# Multi_HUTSCHIENE_EXT_1_2.net
KiCad netlist of a schematic drawn in Altium Designer
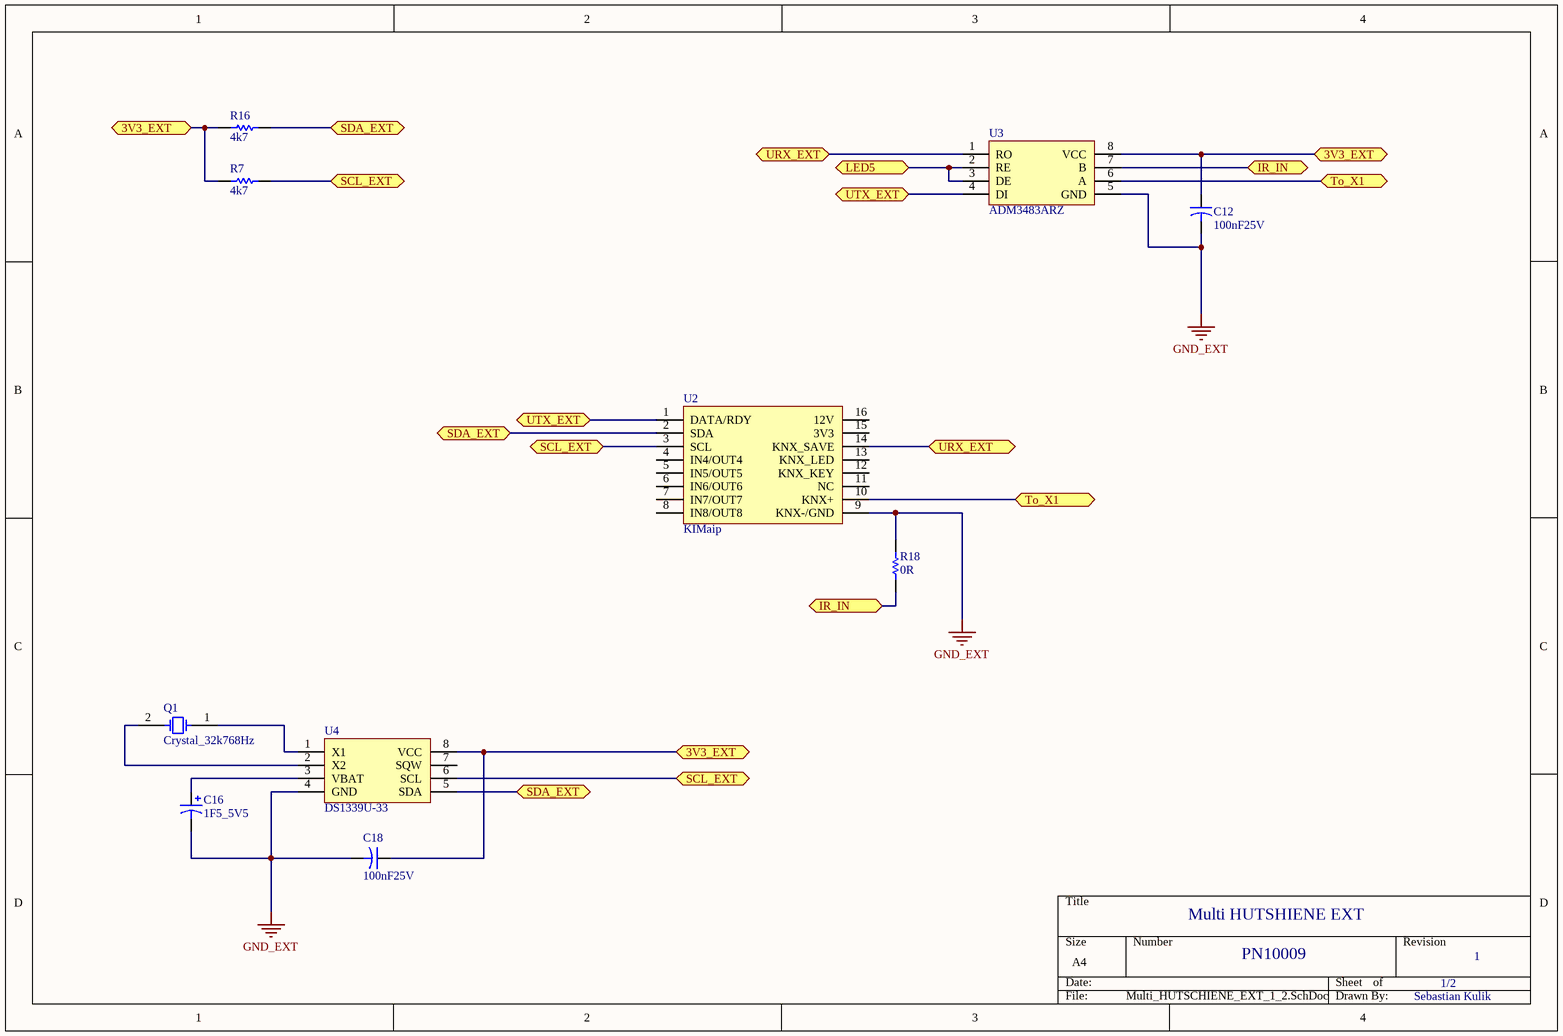
[diagram p0: Multi_HUTSCHIENE_EXT_1_2.SchDoc]

(export (version "E")
  (design (tool "Eeschema 10.0.6"))
  (components
    (comp (ref "C12")
      (value "100nF25V")
      (footprint "C0402")
      (description "AVX, X5R, 10%, 25V")
      (fields
        (field (name "MANUFACTURER") "AVX")
        (field (name "Comment") "100nF25V_0402")
        (field (name "PUBLISHER") "Sebastian Kulik")
      )
      (libsource (lib "Capacitors") (part "100nF25V_0402"))
    )
    (comp (ref "C16")
      (value "1F5_5V5")
      (footprint "Goldcap_B")
      (description "Panasonic, F series")
      (fields
        (field (name "MANUFACTURER") "Panasonic")
        (field (name "Comment") "1F5_5V5_POL")
        (field (name "PUBLISHER") "Sebastian Kulik")
      )
      (libsource (lib "Capacitors") (part "1F5_5V5_POL"))
    )
    (comp (ref "C18")
      (value "100nF25V")
      (footprint "C0402")
      (description "AVX, X5R, 10%, 25V")
      (fields
        (field (name "MANUFACTURER") "AVX")
        (field (name "Comment") "100nF25V_0402")
        (field (name "PUBLISHER") "Sebastian Kulik")
      )
      (libsource (lib "Capacitors") (part "100nF25V_0402"))
    )
    (comp (ref "Q1")
      (value "Crystal_32k768Hz")
      (footprint "VT-200")
      (description "Crystal, 32.768kHz")
      (fields (field (name "MANUFACTURER") "Seiko") (field (name "PUBLISHER") "Sebastian Kulik"))
      (libsource (lib "Passives") (part "Crystal_32k768Hz"))
    )
    (comp (ref "R7")
      (value "4k7")
      (footprint "R0402")
      (description "Vishay CRCW series, 63mW, 1%")
      (fields
        (field (name "MANUFACTURER") "Vishay")
        (field (name "Comment") "4k7_0402")
        (field (name "PUBLISHER") "Sebastian Kulik")
      )
      (libsource (lib "Resistors") (part "4k7_0402"))
    )
    (comp (ref "R16")
      (value "4k7")
      (footprint "R0402")
      (description "Vishay CRCW series, 63mW, 1%")
      (fields
        (field (name "MANUFACTURER") "Vishay")
        (field (name "Comment") "4k7_0402")
        (field (name "PUBLISHER") "Sebastian Kulik")
      )
      (libsource (lib "Resistors") (part "4k7_0402"))
    )
    (comp (ref "R18")
      (value "0R")
      (footprint "R0603(1608)")
      (description "Vishay, CRCW series, 100mW")
      (fields
        (field (name "MANUFACTURER") "Vishay")
        (field (name "Comment") "0R_0603")
        (field (name "PUBLISHER") "Sebastian Kulik")
      )
      (libsource (lib "Resistors") (part "0R_0603"))
    )
    (comp (ref "U2")
      (value "KIMaip")
      (footprint "KIMaip")
      (description "PoE, 12V")
      (fields (field (name "MANUFACTURER") "Tapko") (field (name "PUBLISHER") "Sebastian Kulik"))
      (libsource (lib "ICs") (part "KIMaip"))
    )
    (comp (ref "U3")
      (value "ADM3483ARZ")
      (footprint "SOIC8_N")
      (description "Transceiver, RS485/422")
      (fields (field (name "MANUFACTURER") "ADI") (field (name "PUBLISHER") "Sebastian Kulik"))
      (libsource (lib "ICs") (part "ADM3483ARZ"))
    )
    (comp (ref "U4")
      (value "DS1339U-33")
      (footprint "uSOP8")
      (description "RTC")
      (fields (field (name "MANUFACTURER") "Dallas") (field (name "PUBLISHER") "Sebastian Kulik"))
      (libsource (lib "ICs") (part "DS1339U-33"))
    )
  )
  (nets
    (net (code "1") (name "/3V3_EXT") (class "Default")
      (node (ref "C12") (pin "1") (pinfunction "1_1") (pintype "passive"))
      (node (ref "C18") (pin "1") (pinfunction "1_1") (pintype "passive"))
      (node (ref "R16") (pin "1") (pinfunction "1_1") (pintype "passive"))
      (node (ref "R7") (pin "1") (pinfunction "1_1") (pintype "passive"))
      (node (ref "U3") (pin "8") (pinfunction "VCC_8") (pintype "power_in"))
      (node (ref "U4") (pin "8") (pinfunction "VCC_8") (pintype "power_in"))
    )
    (net (code "2") (name "/IR_IN") (class "Default")
      (node (ref "R18") (pin "1") (pinfunction "1_1") (pintype "passive"))
      (node (ref "U3") (pin "7") (pinfunction "B_7") (pintype "passive"))
    )
    (net (code "3") (name "/LED5") (class "Default")
      (node (ref "U3") (pin "2") (pinfunction "RE_2") (pintype "passive"))
      (node (ref "U3") (pin "3") (pinfunction "DE_3") (pintype "passive"))
    )
    (net (code "4") (name "/SCL_EXT") (class "Default")
      (node (ref "R7") (pin "2") (pinfunction "2_2") (pintype "passive"))
      (node (ref "U2") (pin "3") (pinfunction "SCL_3") (pintype "passive"))
      (node (ref "U4") (pin "6") (pinfunction "SCL_6") (pintype "passive"))
    )
    (net (code "5") (name "/SDA_EXT") (class "Default")
      (node (ref "R16") (pin "2") (pinfunction "2_2") (pintype "passive"))
      (node (ref "U2") (pin "2") (pinfunction "SDA_2") (pintype "passive"))
      (node (ref "U4") (pin "5") (pinfunction "SDA_5") (pintype "passive"))
    )
    (net (code "6") (name "/To_X1") (class "Default")
      (node (ref "U2") (pin "10") (pinfunction "KNX+_10") (pintype "passive"))
      (node (ref "U3") (pin "6") (pinfunction "A_6") (pintype "passive"))
    )
    (net (code "7") (name "/URX_EXT") (class "Default")
      (node (ref "U2") (pin "14") (pinfunction "KNX_SAVE_14") (pintype "passive"))
      (node (ref "U3") (pin "1") (pinfunction "RO_1") (pintype "passive"))
    )
    (net (code "8") (name "/UTX_EXT") (class "Default")
      (node (ref "U2") (pin "1") (pinfunction "DATA/RDY_1") (pintype "passive"))
      (node (ref "U3") (pin "4") (pinfunction "DI_4") (pintype "passive"))
    )
    (net (code "9") (name "GND_EXT") (class "Default")
      (node (ref "C12") (pin "2") (pinfunction "2_2") (pintype "passive"))
      (node (ref "C16") (pin "2") (pinfunction "2_2") (pintype "passive"))
      (node (ref "C18") (pin "2") (pinfunction "2_2") (pintype "passive"))
      (node (ref "R18") (pin "2") (pinfunction "2_2") (pintype "passive"))
      (node (ref "U2") (pin "9") (pinfunction "KNX-/GND_9") (pintype "passive"))
      (node (ref "U3") (pin "5") (pinfunction "GND_5") (pintype "passive"))
      (node (ref "U4") (pin "4") (pinfunction "GND_4") (pintype "passive"))
    )
    (net (code "10") (name "Net-(Q1-E{slash}D)") (class "Default")
      (node (ref "Q1") (pin "1") (pinfunction "E/D_1") (pintype "passive"))
      (node (ref "U4") (pin "1") (pinfunction "X1_1") (pintype "passive"))
    )
    (net (code "11") (name "Net-(Q1-GND)") (class "Default")
      (node (ref "Q1") (pin "2") (pinfunction "GND_2") (pintype "passive"))
      (node (ref "U4") (pin "2") (pinfunction "X2_2") (pintype "passive"))
    )
    (net (code "12") (name "Net-(U4-VBAT)") (class "Default")
      (node (ref "C16") (pin "1") (pinfunction "1_1") (pintype "passive"))
      (node (ref "U4") (pin "3") (pinfunction "VBAT_3") (pintype "passive"))
    )
    (net (code "13") (name "unconnected-(U2-3V3-Pad15)") (class "Default")
      (node (ref "U2") (pin "15") (pinfunction "3V3_15") (pintype "passive"))
    )
    (net (code "14") (name "unconnected-(U2-12V-Pad16)") (class "Default")
      (node (ref "U2") (pin "16") (pinfunction "12V_16") (pintype "passive"))
    )
    (net (code "15") (name "unconnected-(U2-IN4{slash}OUT4-Pad4)") (class "Default")
      (node (ref "U2") (pin "4") (pinfunction "IN4/OUT4_4") (pintype "passive"))
    )
    (net (code "16") (name "unconnected-(U2-IN5{slash}OUT5-Pad5)") (class "Default")
      (node (ref "U2") (pin "5") (pinfunction "IN5/OUT5_5") (pintype "passive"))
    )
    (net (code "17") (name "unconnected-(U2-IN6{slash}OUT6-Pad6)") (class "Default")
      (node (ref "U2") (pin "6") (pinfunction "IN6/OUT6_6") (pintype "passive"))
    )
    (net (code "18") (name "unconnected-(U2-IN7{slash}OUT7-Pad7)") (class "Default")
      (node (ref "U2") (pin "7") (pinfunction "IN7/OUT7_7") (pintype "passive"))
    )
    (net (code "19") (name "unconnected-(U2-IN8{slash}OUT8-Pad8)") (class "Default")
      (node (ref "U2") (pin "8") (pinfunction "IN8/OUT8_8") (pintype "power_in"))
    )
    (net (code "20") (name "unconnected-(U2-KNX_KEY-Pad12)") (class "Default")
      (node (ref "U2") (pin "12") (pinfunction "KNX_KEY_12") (pintype "passive"))
    )
    (net (code "21") (name "unconnected-(U2-KNX_LED-Pad13)") (class "Default")
      (node (ref "U2") (pin "13") (pinfunction "KNX_LED_13") (pintype "passive"))
    )
    (net (code "22") (name "unconnected-(U2-NC-Pad11)") (class "Default")
      (node (ref "U2") (pin "11") (pinfunction "NC_11") (pintype "passive"))
    )
    (net (code "23") (name "unconnected-(U4-SQW-Pad7)") (class "Default")
      (node (ref "U4") (pin "7") (pinfunction "SQW_7") (pintype "passive"))
    )
  )
)
